# sot-mosfet-proto__TOP_LEVEL__A.net
KiCad netlist of a schematic drawn in Altium Designer
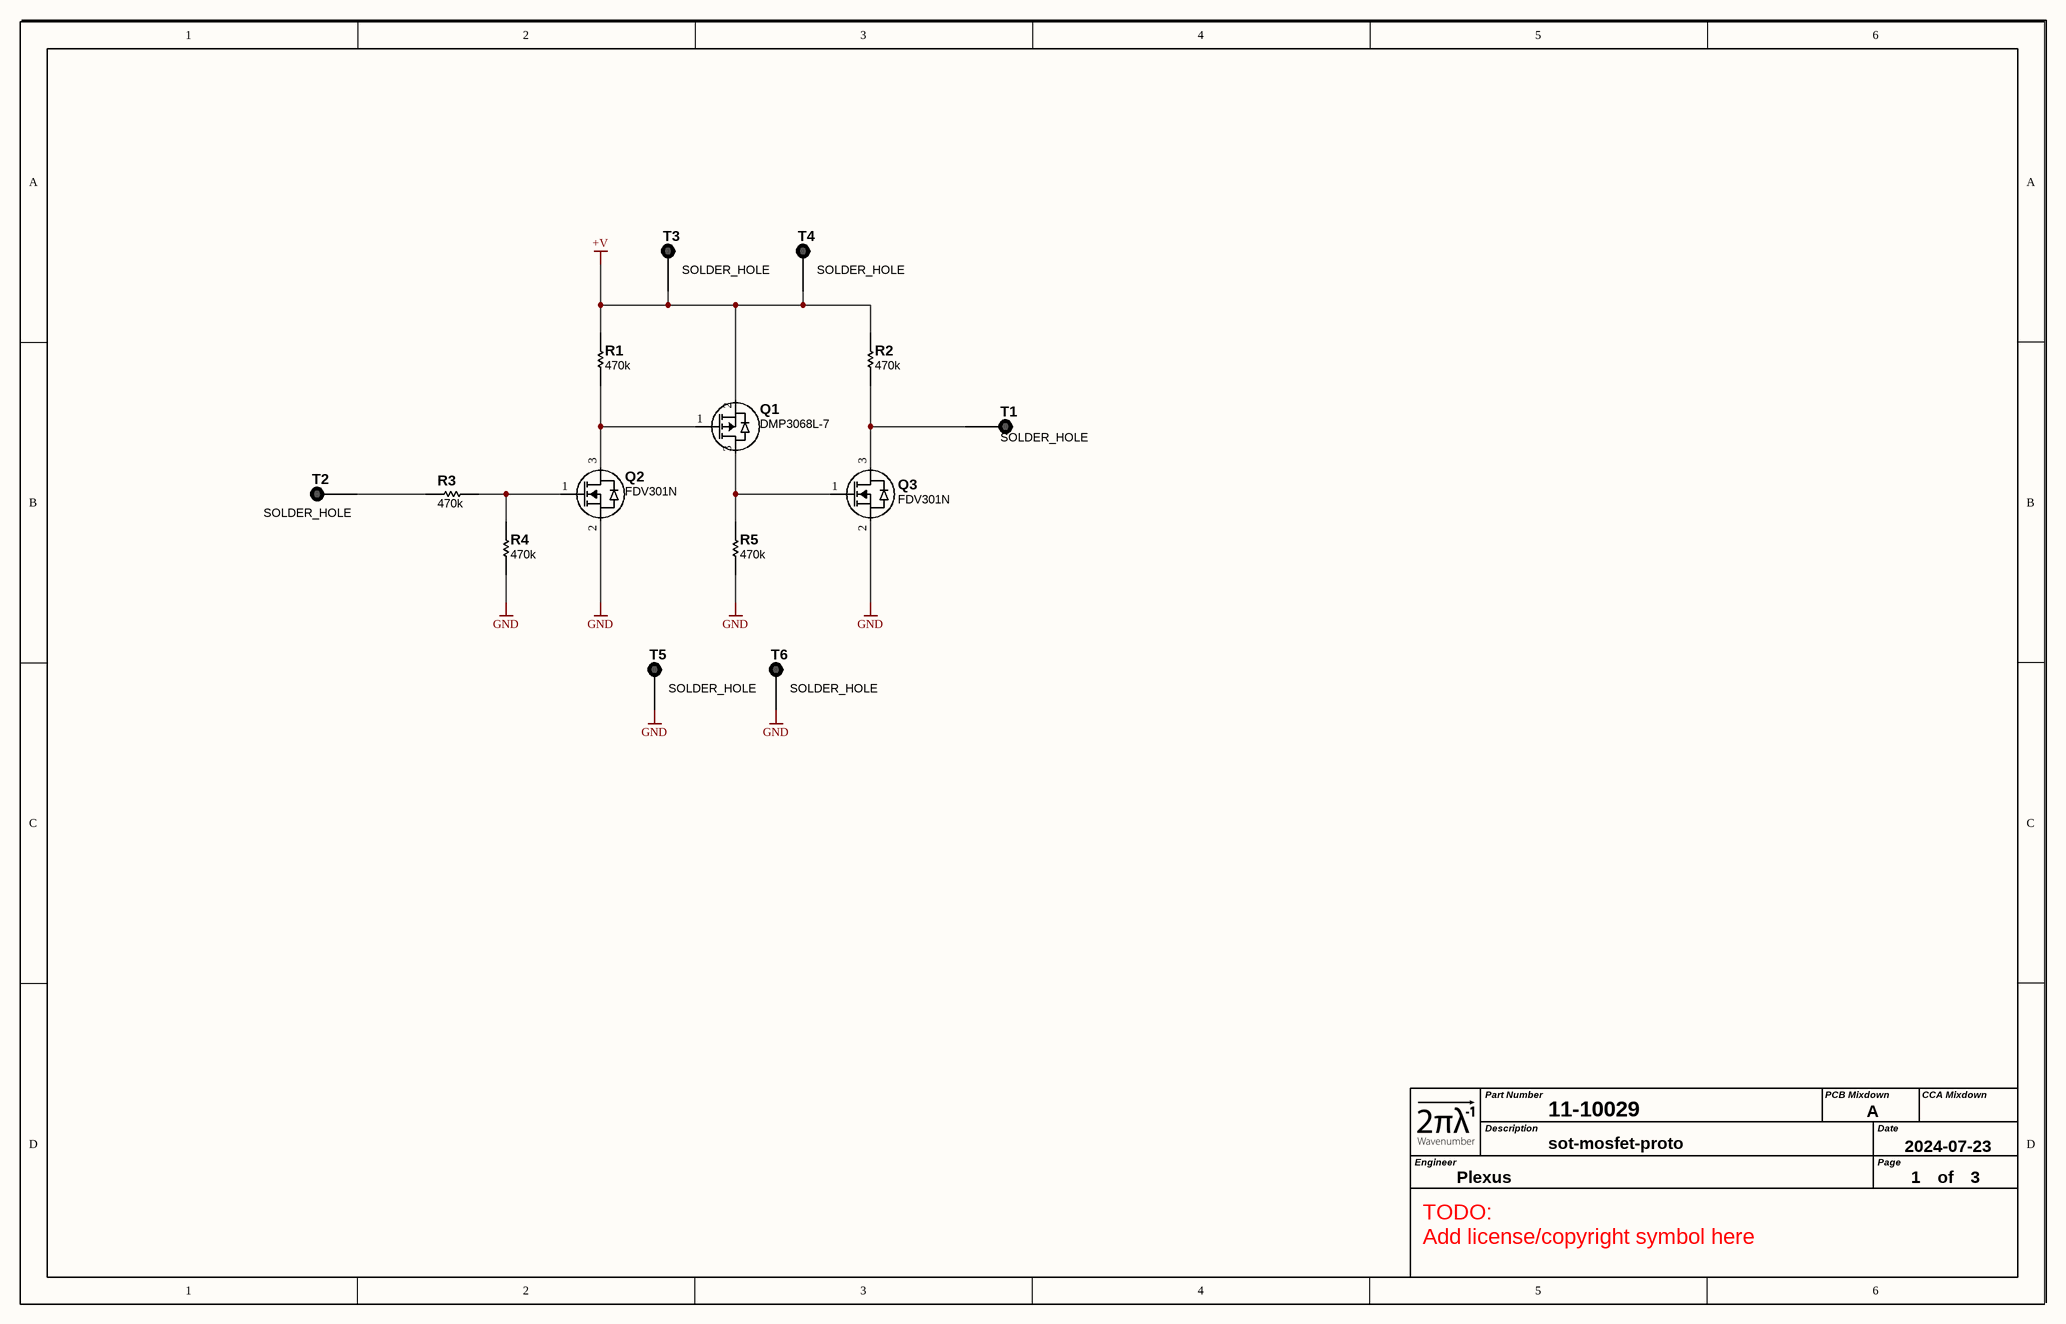
[diagram p0: sot-mosfet-proto__TOP_LEVEL__A.SchDoc]

(export (version "E")
  (design (tool "Eeschema 10.0.6"))
  (components
    (comp (ref "Q1")
      (value "DMP3068L-7")
      (footprint "SOT-23")
      (description "MOSFET P-CH 30V 3.9A SOT23")
      (fields (field (name "MANUFACTURER") "Diodes"))
      (libsource (lib "wn__Transistor") (part "DMP3068L-7"))
    )
    (comp (ref "Q2")
      (value "FDV301N")
      (footprint "SOT-23")
      (description "MOSFET N-CH 25V 220MA SOT-23")
      (fields (field (name "MANUFACTURER") "Fairchild Semiconductor"))
      (libsource (lib "wn__Transistor") (part "FDV301N"))
    )
    (comp (ref "Q3")
      (value "FDV301N")
      (footprint "SOT-23")
      (description "MOSFET N-CH 25V 220MA SOT-23")
      (fields (field (name "MANUFACTURER") "Fairchild Semiconductor"))
      (libsource (lib "wn__Transistor") (part "FDV301N"))
    )
    (comp (ref "R1")
      (value "470k")
      (footprint "R0603_0.55MM_MD")
      (description "RES 470K OHM 1/10W 1% 0603 SMD")
      (fields
        (field (name "MANUFACTURER PART NUMBER") "ERJ-3EKF4703V")
        (field (name "MANUFACTURER") "Panasonic Electronic Components")
      )
      (libsource (lib "Resistors - Panasonic - AEC-Q200") (part "R_2P"))
    )
    (comp (ref "R2")
      (value "470k")
      (footprint "R0603_0.55MM_MD")
      (description "RES 470K OHM 1/10W 1% 0603 SMD")
      (fields
        (field (name "MANUFACTURER PART NUMBER") "ERJ-3EKF4703V")
        (field (name "MANUFACTURER") "Panasonic Electronic Components")
      )
      (libsource (lib "Resistors - Panasonic - AEC-Q200") (part "R_2P"))
    )
    (comp (ref "R3")
      (value "470k")
      (footprint "R0603_0.55MM_MD")
      (description "RES 470K OHM 1/10W 1% 0603 SMD")
      (fields
        (field (name "MANUFACTURER PART NUMBER") "ERJ-3EKF4703V")
        (field (name "MANUFACTURER") "Panasonic Electronic Components")
      )
      (libsource (lib "Resistors - Panasonic - AEC-Q200") (part "R_2P"))
    )
    (comp (ref "R4")
      (value "470k")
      (footprint "R0603_0.55MM_MD")
      (description "RES 470K OHM 1/10W 1% 0603 SMD")
      (fields
        (field (name "MANUFACTURER PART NUMBER") "ERJ-3EKF4703V")
        (field (name "MANUFACTURER") "Panasonic Electronic Components")
      )
      (libsource (lib "Resistors - Panasonic - AEC-Q200") (part "R_2P"))
    )
    (comp (ref "R5")
      (value "470k")
      (footprint "R0603_0.55MM_MD")
      (description "RES 470K OHM 1/10W 1% 0603 SMD")
      (fields
        (field (name "MANUFACTURER PART NUMBER") "ERJ-3EKF4703V")
        (field (name "MANUFACTURER") "Panasonic Electronic Components")
      )
      (libsource (lib "Resistors - Panasonic - AEC-Q200") (part "R_2P"))
    )
    (comp (ref "T1")
      (value "SOLDER_HOLE")
      (footprint "SOLDER_HOLE -  22AWG")
      (description "A Generic Hole for attaching flying leads")
      (libsource (lib "wn__Connector__wire_to_board") (part "SOLDER_HOLE"))
    )
    (comp (ref "T2")
      (value "SOLDER_HOLE")
      (footprint "SOLDER_HOLE -  24AWG")
      (description "A Generic Hole for attaching flying leads")
      (libsource (lib "wn__Connector__wire_to_board") (part "SOLDER_HOLE"))
    )
    (comp (ref "T3")
      (value "SOLDER_HOLE")
      (footprint "SOLDER_HOLE -  22AWG")
      (description "A Generic Hole for attaching flying leads")
      (libsource (lib "wn__Connector__wire_to_board") (part "SOLDER_HOLE"))
    )
    (comp (ref "T4")
      (value "SOLDER_HOLE")
      (footprint "SOLDER_HOLE -  22AWG")
      (description "A Generic Hole for attaching flying leads")
      (libsource (lib "wn__Connector__wire_to_board") (part "SOLDER_HOLE"))
    )
    (comp (ref "T5")
      (value "SOLDER_HOLE")
      (footprint "SOLDER_HOLE -  22AWG")
      (description "A Generic Hole for attaching flying leads")
      (libsource (lib "wn__Connector__wire_to_board") (part "SOLDER_HOLE"))
    )
    (comp (ref "T6")
      (value "SOLDER_HOLE")
      (footprint "SOLDER_HOLE -  22AWG")
      (description "A Generic Hole for attaching flying leads")
      (libsource (lib "wn__Connector__wire_to_board") (part "SOLDER_HOLE"))
    )
  )
  (nets
    (net (code "1") (name "+V") (class "Default")
      (node (ref "Q1") (pin "2") (pinfunction "S_2") (pintype "passive"))
      (node (ref "R1") (pin "2") (pinfunction "2_2") (pintype "passive"))
      (node (ref "R2") (pin "2") (pinfunction "2_2") (pintype "passive"))
      (node (ref "T3") (pin "1") (pinfunction "1_1") (pintype "passive"))
      (node (ref "T4") (pin "1") (pinfunction "1_1") (pintype "passive"))
    )
    (net (code "2") (name "GND") (class "Default")
      (node (ref "Q2") (pin "2") (pinfunction "S_2") (pintype "passive"))
      (node (ref "Q3") (pin "2") (pinfunction "S_2") (pintype "passive"))
      (node (ref "R4") (pin "1") (pinfunction "1_1") (pintype "passive"))
      (node (ref "R5") (pin "1") (pinfunction "1_1") (pintype "passive"))
      (node (ref "T5") (pin "1") (pinfunction "1_1") (pintype "passive"))
      (node (ref "T6") (pin "1") (pinfunction "1_1") (pintype "passive"))
    )
    (net (code "3") (name "Net-(Q1-D)") (class "Default")
      (node (ref "Q1") (pin "3") (pinfunction "D_3") (pintype "passive"))
      (node (ref "Q3") (pin "1") (pinfunction "G_1") (pintype "passive"))
      (node (ref "R5") (pin "2") (pinfunction "2_2") (pintype "passive"))
    )
    (net (code "4") (name "Net-(Q1-G)") (class "Default")
      (node (ref "Q1") (pin "1") (pinfunction "G_1") (pintype "passive"))
      (node (ref "Q2") (pin "3") (pinfunction "D_3") (pintype "passive"))
      (node (ref "R1") (pin "1") (pinfunction "1_1") (pintype "passive"))
    )
    (net (code "5") (name "Net-(Q2-G)") (class "Default")
      (node (ref "Q2") (pin "1") (pinfunction "G_1") (pintype "passive"))
      (node (ref "R3") (pin "1") (pinfunction "1_1") (pintype "passive"))
      (node (ref "R4") (pin "2") (pinfunction "2_2") (pintype "passive"))
    )
    (net (code "6") (name "Net-(Q3-D)") (class "Default")
      (node (ref "Q3") (pin "3") (pinfunction "D_3") (pintype "passive"))
      (node (ref "R2") (pin "1") (pinfunction "1_1") (pintype "passive"))
      (node (ref "T1") (pin "1") (pinfunction "1_1") (pintype "passive"))
    )
    (net (code "7") (name "Net-(R3-Pad2)") (class "Default")
      (node (ref "R3") (pin "2") (pinfunction "2_2") (pintype "passive"))
      (node (ref "T2") (pin "1") (pinfunction "1_1") (pintype "passive"))
    )
  )
)
